# Sheet1.net
KiCad netlist of a schematic drawn in Altium Designer
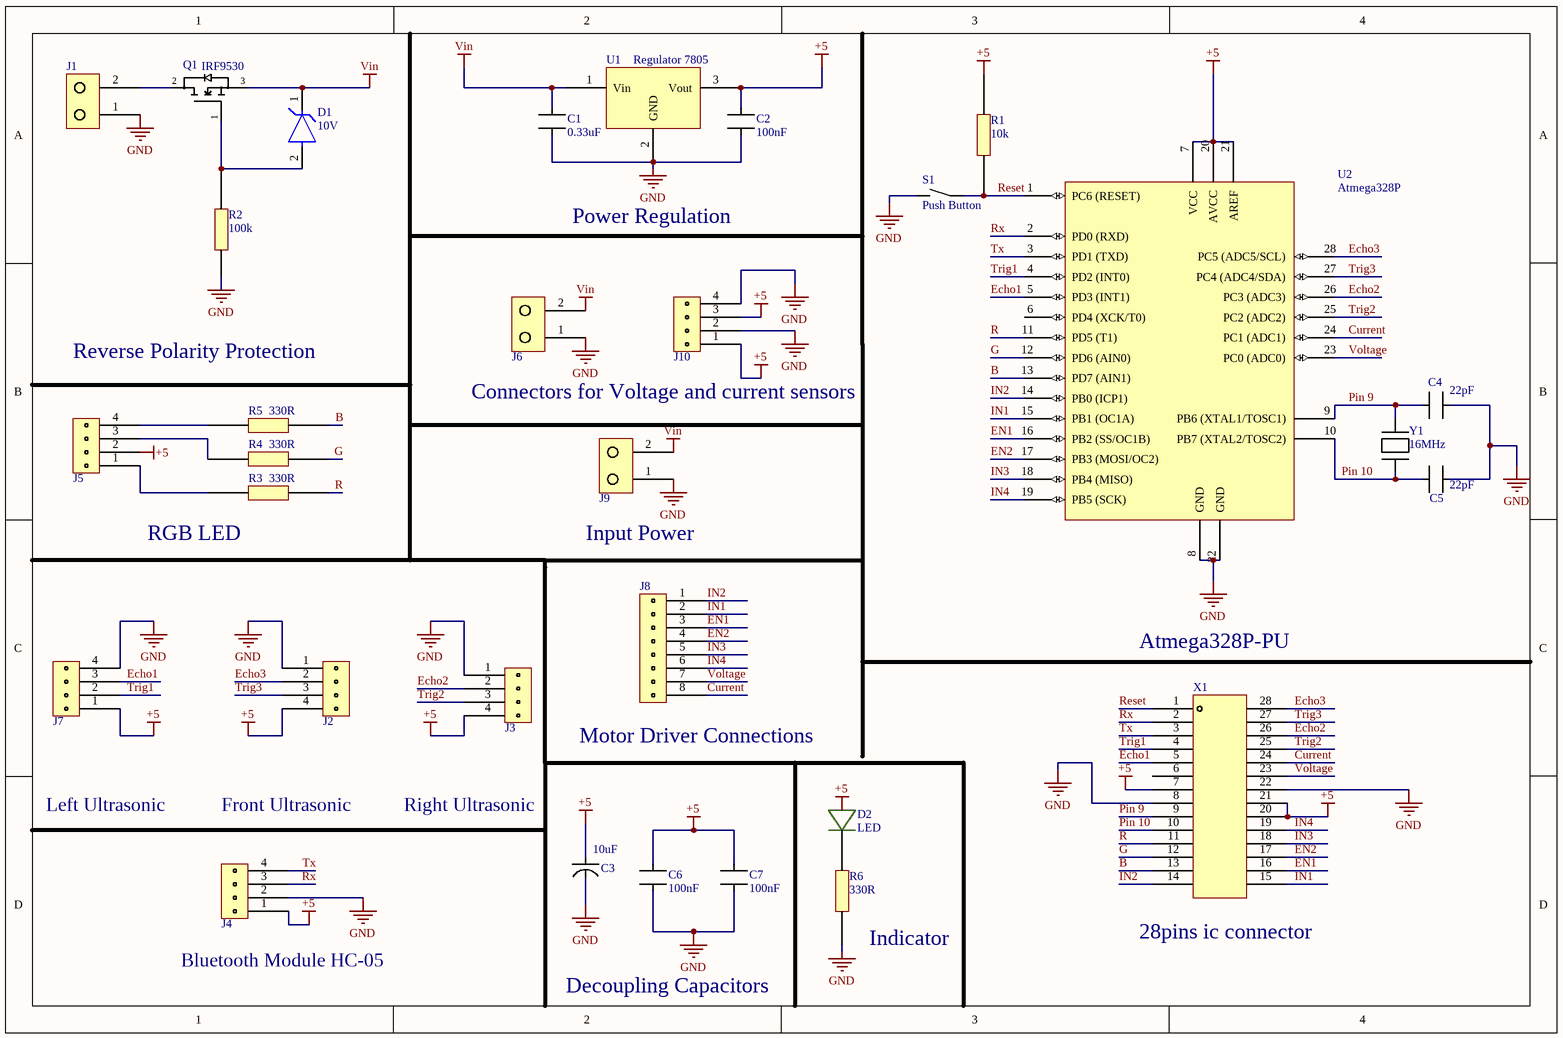
[diagram p0: Sheet1.SchDoc]

(export (version "E")
  (design (tool "Eeschema 10.0.6"))
  (components
    (comp (ref "C1")
      (value "0.33uF")
      (footprint "Capacitor 100nF THT")
      (libsource (lib "Schlib1") (part "Capacitor 100nF THT"))
    )
    (comp (ref "C2")
      (value "100nF")
      (footprint "Capacitor 100nF THT")
      (libsource (lib "Schlib1") (part "Capacitor 100nF THT"))
    )
    (comp (ref "C3")
      (value "10uF")
      (footprint "Pol cap 10uF")
      (libsource (lib "Schlib1") (part "Capacitor (POL) 10uF THT"))
    )
    (comp (ref "C4")
      (value "22pF")
      (footprint "Capacitor 22pF THT")
      (libsource (lib "Schlib1") (part "Capacitor 22pF THT"))
    )
    (comp (ref "C5")
      (value "22pF")
      (footprint "Capacitor 22pF THT")
      (libsource (lib "Schlib1") (part "Capacitor 22pF THT"))
    )
    (comp (ref "C6")
      (value "100nF")
      (footprint "Capacitor 100nF THT")
      (libsource (lib "Schlib1") (part "Capacitor 100nF THT"))
    )
    (comp (ref "C7")
      (value "100nF")
      (footprint "Capacitor 100nF THT")
      (libsource (lib "Schlib1") (part "Capacitor 100nF THT"))
    )
    (comp (ref "D1")
      (value "10V")
      (footprint "FP-017AH-MFG")
      (description "1N4740ATR 1N4740 Series 1 W 10 V 10 uA Through Hole Zener Diode - DO-41")
      (fields (field (name "TOLERANCE") "5%"))
      (libsource (lib "Altium Content Vault") (part "f813f71cba58e380607f5dd3caf9714"))
    )
    (comp (ref "D2") (value "LED") (footprint "Green Led 5mm") (libsource (lib "Schlib1") (part "Green LED")))
    (comp (ref "J1")
      (value "Teminal block 2pins")
      (footprint "Terminal Block")
      (libsource (lib "Schlib1") (part "Teminal block 2pins"))
    )
    (comp (ref "J2")
      (value "Pin Headers 4 pins")
      (footprint "Pin Headers 4 pins")
      (libsource (lib "") (part "Pin Headers 4 pins_1"))
    )
    (comp (ref "J3")
      (value "Pin Headers 4 pins")
      (footprint "Pin Headers 4 pins")
      (libsource (lib "") (part "Pin Headers 4 pins_1"))
    )
    (comp (ref "J4")
      (value "Pin Headers 4 pins")
      (footprint "Pin Headers 4 pins")
      (libsource (lib "Schlib1") (part "Pin Headers 4 pins"))
    )
    (comp (ref "J5")
      (value "Pin Headers 4 pins")
      (footprint "Pin Headers 4 pins")
      (libsource (lib "Schlib1") (part "Pin Headers 4 pins"))
    )
    (comp (ref "J6")
      (value "Teminal block 2pins")
      (footprint "Terminal Block")
      (libsource (lib "Schlib1") (part "Teminal block 2pins"))
    )
    (comp (ref "J7")
      (value "Pin Headers 4 pins")
      (footprint "Pin Headers 4 pins")
      (libsource (lib "Schlib1") (part "Pin Headers 4 pins"))
    )
    (comp (ref "J8")
      (value "Pin Headers 8 Pin Female")
      (footprint "Pin Headers 8 Pin Female")
      (libsource (lib "Schlib1") (part "Pin Headers 8 Pin Female"))
    )
    (comp (ref "J9")
      (value "Teminal block 2pins")
      (footprint "Terminal Block")
      (libsource (lib "Schlib1") (part "Teminal block 2pins"))
    )
    (comp (ref "J10")
      (value "Pin Headers 4 pins")
      (footprint "Pin Headers 4 pins")
      (libsource (lib "Schlib1") (part "Pin Headers 4 pins"))
    )
    (comp (ref "Q1") (value "IRF9530") (footprint "IRF9530") (libsource (lib "Schlib1") (part "IRF9530")))
    (comp (ref "R1")
      (value "10k")
      (footprint "Carbon Resistor 1k Ohm 0.25W")
      (libsource (lib "Schlib1") (part "Resistor tht"))
    )
    (comp (ref "R2")
      (value "100k")
      (footprint "Carbon Resistor 10k Ohm 0.25W")
      (libsource (lib "Schlib1") (part "Resistor 10k Ohms THT"))
    )
    (comp (ref "R3")
      (value "330R")
      (footprint "Carbon Resistor 1k Ohm 0.25W")
      (libsource (lib "") (part "Resistor tht_1"))
    )
    (comp (ref "R4")
      (value "330R")
      (footprint "Carbon Resistor 1k Ohm 0.25W")
      (libsource (lib "") (part "Resistor tht_1"))
    )
    (comp (ref "R5")
      (value "330R")
      (footprint "Carbon Resistor 1k Ohm 0.25W")
      (libsource (lib "") (part "Resistor tht_1"))
    )
    (comp (ref "R6")
      (value "330R")
      (footprint "Carbon Resistor 1k Ohm 0.25W")
      (libsource (lib "Schlib1") (part "Resistor tht"))
    )
    (comp (ref "S1")
      (value "Push Button")
      (footprint "PushButton 2 pins")
      (libsource (lib "Schlib1") (part "Push Button"))
    )
    (comp (ref "U1")
      (value "Regulator 7805")
      (footprint "Regulator LM7805 THT")
      (libsource (lib "Schlib1") (part "Regulator 7805"))
    )
    (comp (ref "U2")
      (value "Atmega328P")
      (footprint "Atmega328P")
      (libsource (lib "Schlib1") (part "Atmega328P"))
    )
    (comp (ref "X1")
      (value "28Pins ic holder")
      (footprint "28 pins ic holder")
      (libsource (lib "Schlib1") (part "28Pins ic holder"))
    )
    (comp (ref "Y1")
      (value "16MHz")
      (footprint "Crystal 16MHz")
      (libsource (lib "Schlib1") (part "16MHz Crystal"))
    )
  )
  (nets
    (net (code "1") (name "+5") (class "Default")
      (node (ref "C2") (pin "2") (pinfunction "2_2") (pintype "passive"))
      (node (ref "C3") (pin "1") (pinfunction "1_1") (pintype "passive"))
      (node (ref "C6") (pin "2") (pinfunction "2_2") (pintype "passive"))
      (node (ref "C7") (pin "2") (pinfunction "2_2") (pintype "passive"))
      (node (ref "D2") (pin "1") (pinfunction "1_1") (pintype "passive"))
      (node (ref "J10") (pin "1") (pinfunction "1_1") (pintype "passive"))
      (node (ref "J10") (pin "3") (pinfunction "3_3") (pintype "passive"))
      (node (ref "J2") (pin "4") (pinfunction "4_4") (pintype "passive"))
      (node (ref "J3") (pin "4") (pinfunction "4_4") (pintype "passive"))
      (node (ref "J4") (pin "1") (pinfunction "1_1") (pintype "passive"))
      (node (ref "J5") (pin "2") (pinfunction "2_2") (pintype "passive"))
      (node (ref "J7") (pin "1") (pinfunction "1_1") (pintype "passive"))
      (node (ref "R1") (pin "1") (pinfunction "1_1") (pintype "passive"))
      (node (ref "U1") (pin "3") (pinfunction "Vout_3") (pintype "passive"))
      (node (ref "U2") (pin "20") (pinfunction "AVCC_20") (pintype "power_in"))
      (node (ref "U2") (pin "21") (pinfunction "AREF_21") (pintype "power_in"))
      (node (ref "U2") (pin "7") (pinfunction "VCC_7") (pintype "power_in"))
      (node (ref "X1") (pin "20") (pinfunction "20_20") (pintype "passive"))
      (node (ref "X1") (pin "21") (pinfunction "21_21") (pintype "passive"))
      (node (ref "X1") (pin "7") (pinfunction "7_7") (pintype "passive"))
    )
    (net (code "2") (name "/B") (class "Default")
      (node (ref "R5") (pin "2") (pinfunction "2_2") (pintype "passive"))
      (node (ref "U2") (pin "13") (pinfunction "PD7_(AIN1)_13") (pintype "bidirectional"))
      (node (ref "X1") (pin "13") (pinfunction "13_13") (pintype "passive"))
    )
    (net (code "3") (name "/Current") (class "Default")
      (node (ref "J8") (pin "8") (pinfunction "8_8") (pintype "passive"))
      (node (ref "U2") (pin "24") (pinfunction "PC1_(ADC1)_24") (pintype "bidirectional"))
      (node (ref "X1") (pin "24") (pinfunction "24_24") (pintype "passive"))
    )
    (net (code "4") (name "/EN1") (class "Default")
      (node (ref "J8") (pin "3") (pinfunction "3_3") (pintype "passive"))
      (node (ref "U2") (pin "16") (pinfunction "PB2_(SS/OC1B)_16") (pintype "bidirectional"))
      (node (ref "X1") (pin "16") (pinfunction "16_16") (pintype "passive"))
    )
    (net (code "5") (name "/EN2") (class "Default")
      (node (ref "J8") (pin "4") (pinfunction "4_4") (pintype "passive"))
      (node (ref "U2") (pin "17") (pinfunction "PB3_(MOSI/OC2)_17") (pintype "bidirectional"))
      (node (ref "X1") (pin "17") (pinfunction "17_17") (pintype "passive"))
    )
    (net (code "6") (name "/Echo1") (class "Default")
      (node (ref "J7") (pin "3") (pinfunction "3_3") (pintype "passive"))
      (node (ref "U2") (pin "5") (pinfunction "PD3_(INT1)_5") (pintype "bidirectional"))
      (node (ref "X1") (pin "5") (pinfunction "5_5") (pintype "passive"))
    )
    (net (code "7") (name "/Echo2") (class "Default")
      (node (ref "J3") (pin "2") (pinfunction "2_2") (pintype "passive"))
      (node (ref "U2") (pin "26") (pinfunction "PC3_(ADC3)_26") (pintype "bidirectional"))
      (node (ref "X1") (pin "26") (pinfunction "26_26") (pintype "passive"))
    )
    (net (code "8") (name "/Echo3") (class "Default")
      (node (ref "J2") (pin "2") (pinfunction "2_2") (pintype "passive"))
      (node (ref "U2") (pin "28") (pinfunction "PC5_(ADC5/SCL)_28") (pintype "bidirectional"))
      (node (ref "X1") (pin "28") (pinfunction "28_28") (pintype "passive"))
    )
    (net (code "9") (name "/G") (class "Default")
      (node (ref "R4") (pin "2") (pinfunction "2_2") (pintype "passive"))
      (node (ref "U2") (pin "12") (pinfunction "PD6_(AIN0)_12") (pintype "bidirectional"))
      (node (ref "X1") (pin "12") (pinfunction "12_12") (pintype "passive"))
    )
    (net (code "10") (name "/IN1") (class "Default")
      (node (ref "J8") (pin "2") (pinfunction "2_2") (pintype "passive"))
      (node (ref "U2") (pin "15") (pinfunction "PB1_(OC1A)_15") (pintype "bidirectional"))
      (node (ref "X1") (pin "15") (pinfunction "15_15") (pintype "passive"))
    )
    (net (code "11") (name "/IN2") (class "Default")
      (node (ref "J8") (pin "1") (pinfunction "1_1") (pintype "passive"))
      (node (ref "U2") (pin "14") (pinfunction "PB0_(ICP1)_14") (pintype "bidirectional"))
      (node (ref "X1") (pin "14") (pinfunction "14_14") (pintype "passive"))
    )
    (net (code "12") (name "/IN3") (class "Default")
      (node (ref "J8") (pin "5") (pinfunction "5_5") (pintype "passive"))
      (node (ref "U2") (pin "18") (pinfunction "PB4_(MISO)_18") (pintype "bidirectional"))
      (node (ref "X1") (pin "18") (pinfunction "18_18") (pintype "passive"))
    )
    (net (code "13") (name "/IN4") (class "Default")
      (node (ref "J8") (pin "6") (pinfunction "6_6") (pintype "passive"))
      (node (ref "U2") (pin "19") (pinfunction "PB5_(SCK)_19") (pintype "bidirectional"))
      (node (ref "X1") (pin "19") (pinfunction "19_19") (pintype "passive"))
    )
    (net (code "14") (name "/Pin 9") (class "Default")
      (node (ref "C4") (pin "2") (pinfunction "2_2") (pintype "passive"))
      (node (ref "U2") (pin "9") (pinfunction "PB6_(XTAL1/TOSC1)_9") (pintype "passive"))
      (node (ref "X1") (pin "9") (pinfunction "9_9") (pintype "passive"))
      (node (ref "Y1") (pin "2") (pinfunction "2_2") (pintype "passive"))
    )
    (net (code "15") (name "/Pin 10") (class "Default")
      (node (ref "C5") (pin "2") (pinfunction "2_2") (pintype "passive"))
      (node (ref "U2") (pin "10") (pinfunction "PB7_(XTAL2/TOSC2)_10") (pintype "passive"))
      (node (ref "X1") (pin "10") (pinfunction "10_10") (pintype "passive"))
      (node (ref "Y1") (pin "1") (pinfunction "1_1") (pintype "passive"))
    )
    (net (code "16") (name "/R") (class "Default")
      (node (ref "R3") (pin "2") (pinfunction "2_2") (pintype "passive"))
      (node (ref "U2") (pin "11") (pinfunction "PD5_(T1)_11") (pintype "bidirectional"))
      (node (ref "X1") (pin "11") (pinfunction "11_11") (pintype "passive"))
    )
    (net (code "17") (name "/Reset") (class "Default")
      (node (ref "R1") (pin "2") (pinfunction "2_2") (pintype "passive"))
      (node (ref "S1") (pin "2") (pinfunction "2_2") (pintype "passive"))
      (node (ref "U2") (pin "1") (pinfunction "PC6_(RESET)_1") (pintype "bidirectional"))
      (node (ref "X1") (pin "1") (pinfunction "1_1") (pintype "passive"))
    )
    (net (code "18") (name "/Rx") (class "Default")
      (node (ref "J4") (pin "3") (pinfunction "3_3") (pintype "passive"))
      (node (ref "U2") (pin "2") (pinfunction "PD0_(RXD)_2") (pintype "bidirectional"))
      (node (ref "X1") (pin "2") (pinfunction "2_2") (pintype "passive"))
    )
    (net (code "19") (name "/Trig1") (class "Default")
      (node (ref "J7") (pin "2") (pinfunction "2_2") (pintype "passive"))
      (node (ref "U2") (pin "4") (pinfunction "PD2_(INT0)_4") (pintype "bidirectional"))
      (node (ref "X1") (pin "4") (pinfunction "4_4") (pintype "passive"))
    )
    (net (code "20") (name "/Trig2") (class "Default")
      (node (ref "J3") (pin "3") (pinfunction "3_3") (pintype "passive"))
      (node (ref "U2") (pin "25") (pinfunction "PC2_(ADC2)_25") (pintype "bidirectional"))
      (node (ref "X1") (pin "25") (pinfunction "25_25") (pintype "passive"))
    )
    (net (code "21") (name "/Trig3") (class "Default")
      (node (ref "J2") (pin "3") (pinfunction "3_3") (pintype "passive"))
      (node (ref "U2") (pin "27") (pinfunction "PC4_(ADC4/SDA)_27") (pintype "bidirectional"))
      (node (ref "X1") (pin "27") (pinfunction "27_27") (pintype "passive"))
    )
    (net (code "22") (name "/Tx") (class "Default")
      (node (ref "J4") (pin "4") (pinfunction "4_4") (pintype "passive"))
      (node (ref "U2") (pin "3") (pinfunction "PD1_(TXD)_3") (pintype "bidirectional"))
      (node (ref "X1") (pin "3") (pinfunction "3_3") (pintype "passive"))
    )
    (net (code "23") (name "/Voltage") (class "Default")
      (node (ref "J8") (pin "7") (pinfunction "7_7") (pintype "passive"))
      (node (ref "U2") (pin "23") (pinfunction "PC0_(ADC0)_23") (pintype "bidirectional"))
      (node (ref "X1") (pin "23") (pinfunction "23_23") (pintype "passive"))
    )
    (net (code "24") (name "GND") (class "Default")
      (node (ref "C1") (pin "1") (pinfunction "1_1") (pintype "passive"))
      (node (ref "C2") (pin "1") (pinfunction "1_1") (pintype "passive"))
      (node (ref "C3") (pin "2") (pinfunction "2_2") (pintype "passive"))
      (node (ref "C4") (pin "1") (pinfunction "1_1") (pintype "passive"))
      (node (ref "C5") (pin "1") (pinfunction "1_1") (pintype "passive"))
      (node (ref "C6") (pin "1") (pinfunction "1_1") (pintype "passive"))
      (node (ref "C7") (pin "1") (pinfunction "1_1") (pintype "passive"))
      (node (ref "J1") (pin "1") (pinfunction "1_1") (pintype "passive"))
      (node (ref "J10") (pin "2") (pinfunction "2_2") (pintype "passive"))
      (node (ref "J10") (pin "4") (pinfunction "4_4") (pintype "passive"))
      (node (ref "J2") (pin "1") (pinfunction "1_1") (pintype "passive"))
      (node (ref "J3") (pin "1") (pinfunction "1_1") (pintype "passive"))
      (node (ref "J4") (pin "2") (pinfunction "2_2") (pintype "passive"))
      (node (ref "J6") (pin "1") (pinfunction "1_1") (pintype "passive"))
      (node (ref "J7") (pin "4") (pinfunction "4_4") (pintype "passive"))
      (node (ref "J9") (pin "1") (pinfunction "1_1") (pintype "passive"))
      (node (ref "R2") (pin "2") (pinfunction "2_2") (pintype "passive"))
      (node (ref "R6") (pin "2") (pinfunction "2_2") (pintype "passive"))
      (node (ref "S1") (pin "1") (pinfunction "1_1") (pintype "passive"))
      (node (ref "U1") (pin "2") (pinfunction "GND_2") (pintype "passive"))
      (node (ref "U2") (pin "22") (pinfunction "GND_22") (pintype "power_in"))
      (node (ref "U2") (pin "8") (pinfunction "GND_8") (pintype "power_in"))
      (node (ref "X1") (pin "22") (pinfunction "22_22") (pintype "passive"))
      (node (ref "X1") (pin "8") (pinfunction "8_8") (pintype "passive"))
    )
    (net (code "25") (name "Net-(D1-A)") (class "Default")
      (node (ref "D1") (pin "2") (pinfunction "A_2") (pintype "passive"))
      (node (ref "Q1") (pin "1") (pinfunction "G_1") (pintype "passive"))
      (node (ref "R2") (pin "1") (pinfunction "1_1") (pintype "passive"))
    )
    (net (code "26") (name "Net-(D2-Pad2)") (class "Default")
      (node (ref "D2") (pin "2") (pinfunction "2_2") (pintype "passive"))
      (node (ref "R6") (pin "1") (pinfunction "1_1") (pintype "passive"))
    )
    (net (code "27") (name "Net-(J5-Pad1)") (class "Default")
      (node (ref "J5") (pin "1") (pinfunction "1_1") (pintype "passive"))
      (node (ref "R3") (pin "1") (pinfunction "1_1") (pintype "passive"))
    )
    (net (code "28") (name "Net-(J5-Pad3)") (class "Default")
      (node (ref "J5") (pin "3") (pinfunction "3_3") (pintype "passive"))
      (node (ref "R4") (pin "1") (pinfunction "1_1") (pintype "passive"))
    )
    (net (code "29") (name "Net-(J5-Pad4)") (class "Default")
      (node (ref "J5") (pin "4") (pinfunction "4_4") (pintype "passive"))
      (node (ref "R5") (pin "1") (pinfunction "1_1") (pintype "passive"))
    )
    (net (code "30") (name "Net-(Q1-D)") (class "Default")
      (node (ref "J1") (pin "2") (pinfunction "2_2") (pintype "passive"))
      (node (ref "Q1") (pin "2") (pinfunction "D_2") (pintype "passive"))
    )
    (net (code "31") (name "Vin") (class "Default")
      (node (ref "C1") (pin "2") (pinfunction "2_2") (pintype "passive"))
      (node (ref "D1") (pin "1") (pinfunction "C_1") (pintype "passive"))
      (node (ref "J6") (pin "2") (pinfunction "2_2") (pintype "passive"))
      (node (ref "J9") (pin "2") (pinfunction "2_2") (pintype "passive"))
      (node (ref "Q1") (pin "3") (pinfunction "S_3") (pintype "passive"))
      (node (ref "U1") (pin "1") (pinfunction "Vin_1") (pintype "passive"))
    )
    (net (code "32") (name "unconnected-(U2-PD4_(XCK{slash}T0)-Pad6)") (class "Default")
      (node (ref "U2") (pin "6") (pinfunction "PD4_(XCK/T0)_6") (pintype "bidirectional"))
    )
    (net (code "33") (name "unconnected-(X1-Pad6)") (class "Default")
      (node (ref "X1") (pin "6") (pinfunction "6_6") (pintype "passive"))
    )
  )
)
